# ITC.net
KiCad netlist of a schematic drawn in EAGLE
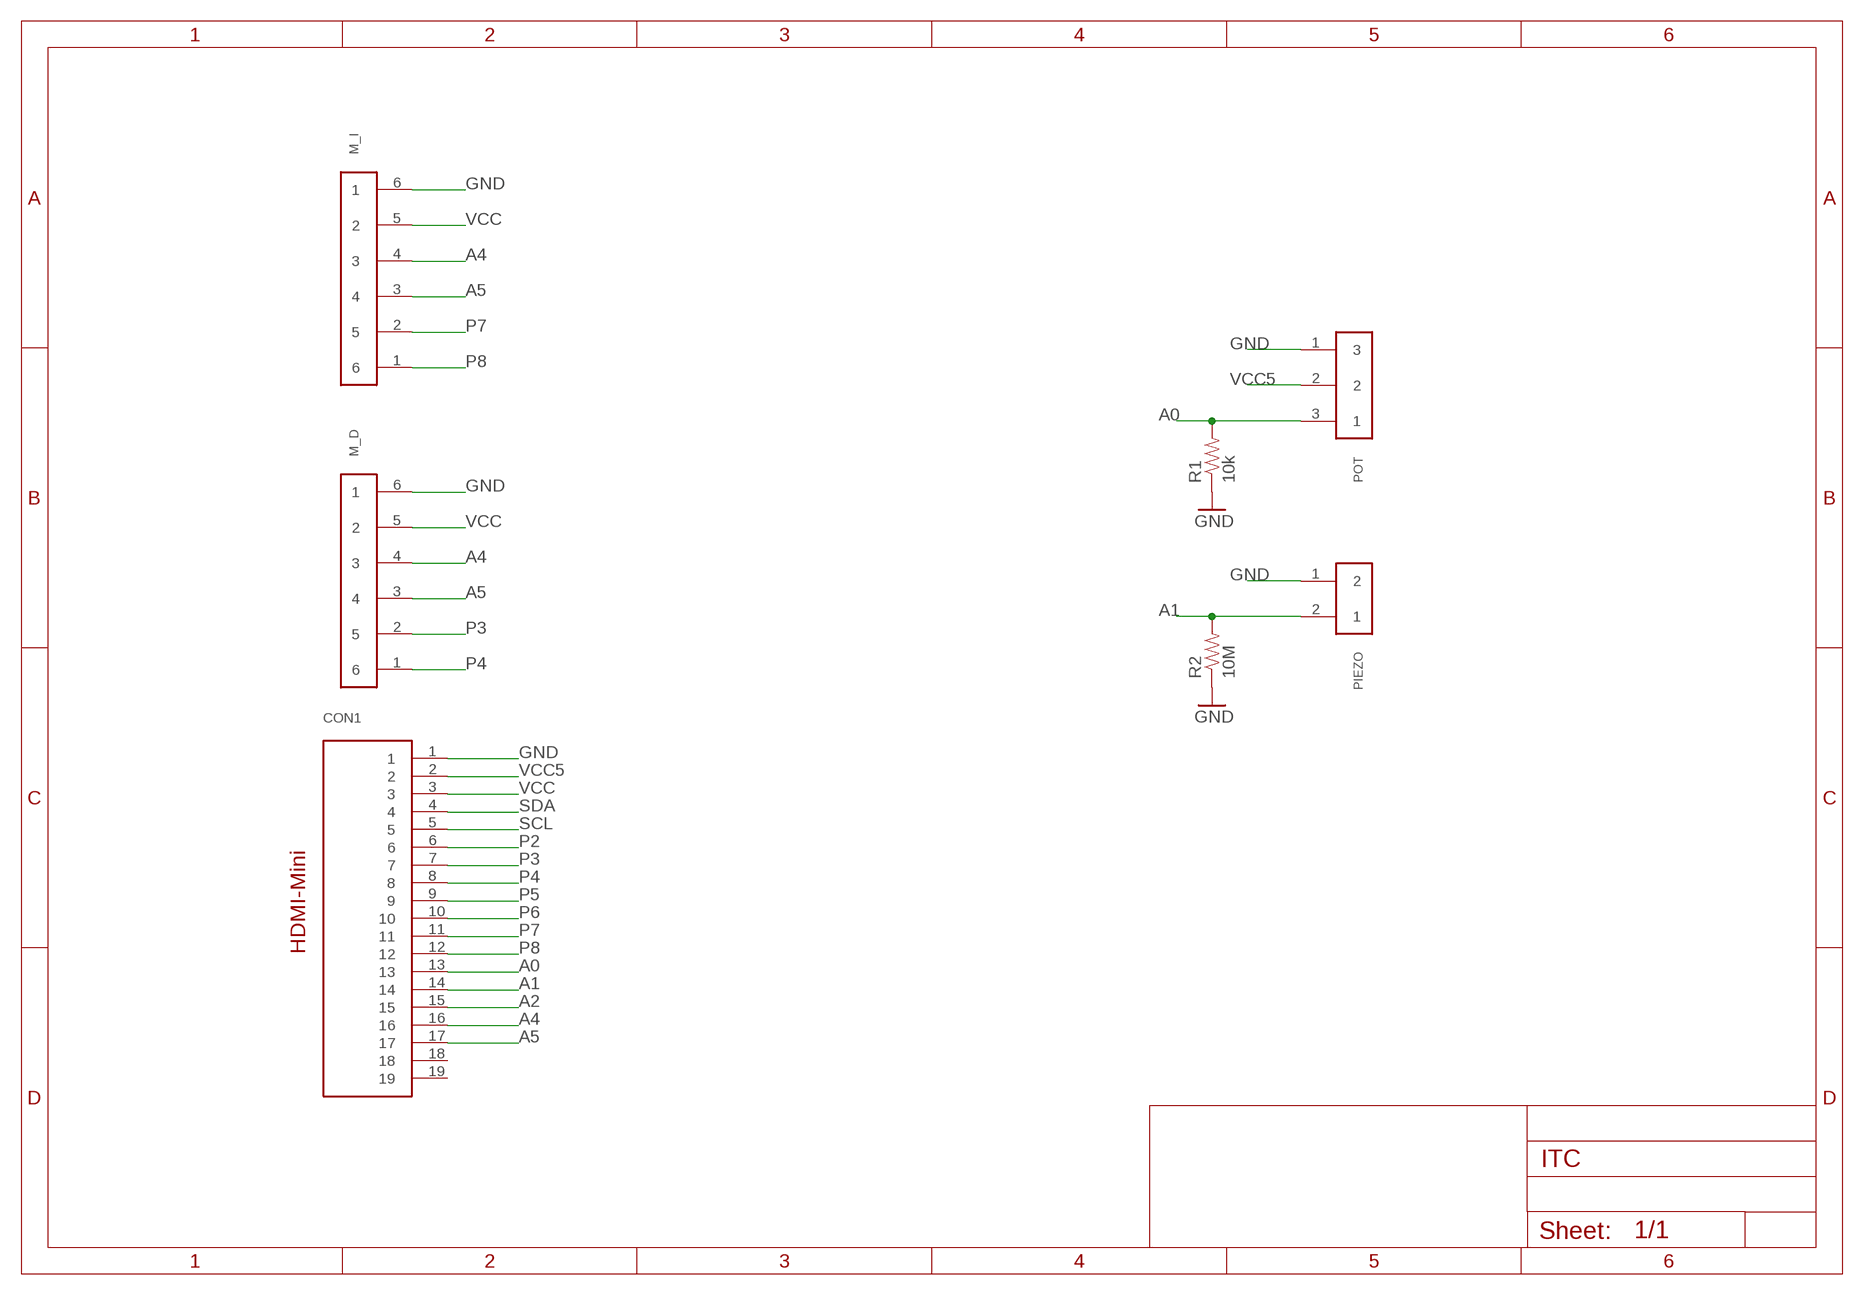
[diagram p0: schematic, sheet 1]

(export (version "E")
  (design (tool "Eeschema 10.0.6"))
  (components
    (comp (ref "CON1")
      (value "HDMIMINI")
      (footprint "eagle-import:HDMIMINI")
      (libsource (lib "eagle-import") (part "HDMIMINI"))
    )
    (comp (ref "M_D")
      (value "653106131822")
      (footprint "eagle-import:653106131822")
      (libsource (lib "eagle-import") (part "653106131822"))
    )
    (comp (ref "M_I")
      (value "653106131822")
      (footprint "eagle-import:653106131822")
      (libsource (lib "eagle-import") (part "653106131822"))
    )
    (comp (ref "PIEZO")
      (value "653102131822")
      (footprint "eagle-import:653102131822")
      (libsource (lib "eagle-import") (part "653102131822"))
    )
    (comp (ref "POT")
      (value "653103131822")
      (footprint "eagle-import:653103131822")
      (libsource (lib "eagle-import") (part "653103131822"))
    )
    (comp (ref "R1")
      (value "10k")
      (footprint "eagle-import:0402-RES")
      (libsource (lib "eagle-import") (part "RESISTOR0402-RES"))
    )
    (comp (ref "R2")
      (value "10M")
      (footprint "eagle-import:0402-RES")
      (libsource (lib "eagle-import") (part "RESISTOR0402-RES"))
    )
  )
  (nets
    (net (code "1") (name "/A0") (class "Default")
      (node (ref "CON1") (pin "13") (pinfunction "13_13") (pintype "bidirectional"))
      (node (ref "POT") (pin "3") (pinfunction "1_3") (pintype "bidirectional"))
      (node (ref "R1") (pin "2") (pinfunction "2_2") (pintype "passive"))
    )
    (net (code "2") (name "/A1") (class "Default")
      (node (ref "CON1") (pin "14") (pinfunction "14_14") (pintype "bidirectional"))
      (node (ref "PIEZO") (pin "2") (pinfunction "1_2") (pintype "bidirectional"))
      (node (ref "R2") (pin "2") (pinfunction "2_2") (pintype "passive"))
    )
    (net (code "3") (name "/A2") (class "Default")
      (node (ref "CON1") (pin "15") (pinfunction "15_15") (pintype "bidirectional"))
    )
    (net (code "4") (name "/A4") (class "Default")
      (node (ref "CON1") (pin "16") (pinfunction "16_16") (pintype "bidirectional"))
      (node (ref "M_D") (pin "4") (pinfunction "3_4") (pintype "bidirectional"))
      (node (ref "M_I") (pin "4") (pinfunction "3_4") (pintype "bidirectional"))
    )
    (net (code "5") (name "/A5") (class "Default")
      (node (ref "CON1") (pin "17") (pinfunction "17_17") (pintype "bidirectional"))
      (node (ref "M_D") (pin "3") (pinfunction "4_3") (pintype "bidirectional"))
      (node (ref "M_I") (pin "3") (pinfunction "4_3") (pintype "bidirectional"))
    )
    (net (code "6") (name "/P2") (class "Default")
      (node (ref "CON1") (pin "6") (pinfunction "6_6") (pintype "bidirectional"))
    )
    (net (code "7") (name "/P3") (class "Default")
      (node (ref "CON1") (pin "7") (pinfunction "7_7") (pintype "bidirectional"))
      (node (ref "M_D") (pin "2") (pinfunction "5_2") (pintype "bidirectional"))
    )
    (net (code "8") (name "/P4") (class "Default")
      (node (ref "CON1") (pin "8") (pinfunction "8_8") (pintype "bidirectional"))
      (node (ref "M_D") (pin "1") (pinfunction "6_1") (pintype "bidirectional"))
    )
    (net (code "9") (name "/P5") (class "Default")
      (node (ref "CON1") (pin "9") (pinfunction "9_9") (pintype "bidirectional"))
    )
    (net (code "10") (name "/P6") (class "Default")
      (node (ref "CON1") (pin "10") (pinfunction "10_10") (pintype "bidirectional"))
    )
    (net (code "11") (name "/P7") (class "Default")
      (node (ref "CON1") (pin "11") (pinfunction "11_11") (pintype "bidirectional"))
      (node (ref "M_I") (pin "2") (pinfunction "5_2") (pintype "bidirectional"))
    )
    (net (code "12") (name "/P8") (class "Default")
      (node (ref "CON1") (pin "12") (pinfunction "12_12") (pintype "bidirectional"))
      (node (ref "M_I") (pin "1") (pinfunction "6_1") (pintype "bidirectional"))
    )
    (net (code "13") (name "/SCL") (class "Default")
      (node (ref "CON1") (pin "5") (pinfunction "5_5") (pintype "bidirectional"))
    )
    (net (code "14") (name "/SDA") (class "Default")
      (node (ref "CON1") (pin "4") (pinfunction "4_4") (pintype "bidirectional"))
    )
    (net (code "15") (name "/VCC") (class "Default")
      (node (ref "CON1") (pin "3") (pinfunction "3_3") (pintype "bidirectional"))
      (node (ref "M_D") (pin "5") (pinfunction "2_5") (pintype "bidirectional"))
      (node (ref "M_I") (pin "5") (pinfunction "2_5") (pintype "bidirectional"))
    )
    (net (code "16") (name "/VCC5") (class "Default")
      (node (ref "CON1") (pin "2") (pinfunction "2_2") (pintype "bidirectional"))
      (node (ref "POT") (pin "2") (pinfunction "2_2") (pintype "bidirectional"))
    )
    (net (code "17") (name "GND") (class "Default")
      (node (ref "CON1") (pin "1") (pinfunction "1_1") (pintype "bidirectional"))
      (node (ref "M_D") (pin "6") (pinfunction "1_6") (pintype "bidirectional"))
      (node (ref "M_I") (pin "6") (pinfunction "1_6") (pintype "bidirectional"))
      (node (ref "PIEZO") (pin "1") (pinfunction "2_1") (pintype "bidirectional"))
      (node (ref "POT") (pin "1") (pinfunction "3_1") (pintype "bidirectional"))
      (node (ref "R1") (pin "1") (pinfunction "1_1") (pintype "passive"))
      (node (ref "R2") (pin "1") (pinfunction "1_1") (pintype "passive"))
    )
    (net (code "18") (name "unconnected-(CON1-Pad18)") (class "Default")
      (node (ref "CON1") (pin "18") (pinfunction "18_18") (pintype "bidirectional"))
    )
    (net (code "19") (name "unconnected-(CON1-Pad19)") (class "Default")
      (node (ref "CON1") (pin "19") (pinfunction "19_19") (pintype "bidirectional"))
    )
  )
)
